# PIXIE_CHROMA_EVAL_PCB.net
KiCad netlist of a schematic drawn in EAGLE
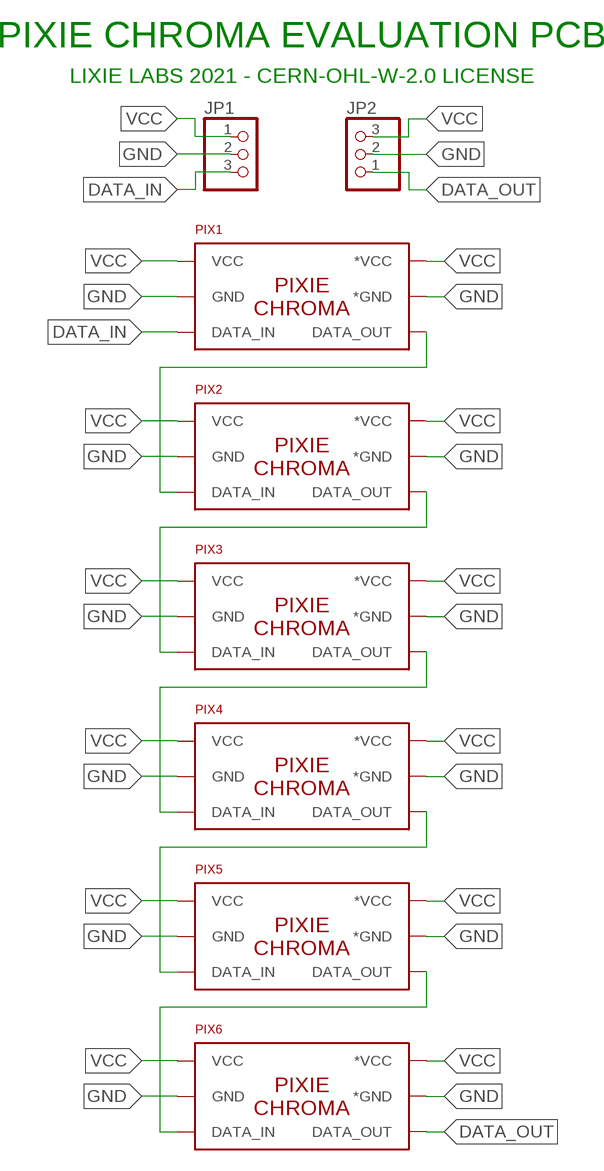
[diagram p0: schematic, sheet 1]

(export (version "E")
  (design (tool "Eeschema 10.0.6"))
  (components
    (comp (ref "JP1")
      (value "PINHD-1X3")
      (footprint "eagle-import:1X03")
      (libsource (lib "eagle-import") (part "PINHD-1X3"))
    )
    (comp (ref "JP2")
      (value "PINHD-1X3")
      (footprint "eagle-import:1X03")
      (libsource (lib "eagle-import") (part "PINHD-1X3"))
    )
    (comp (ref "PIX1")
      (value "CHROMA")
      (footprint "eagle-import:CHROMA")
      (libsource (lib "eagle-import") (part "CHROMA"))
    )
    (comp (ref "PIX2")
      (value "CHROMA")
      (footprint "eagle-import:CHROMA")
      (libsource (lib "eagle-import") (part "CHROMA"))
    )
    (comp (ref "PIX3")
      (value "CHROMA")
      (footprint "eagle-import:CHROMA")
      (libsource (lib "eagle-import") (part "CHROMA"))
    )
    (comp (ref "PIX4")
      (value "CHROMA")
      (footprint "eagle-import:CHROMA")
      (libsource (lib "eagle-import") (part "CHROMA"))
    )
    (comp (ref "PIX5")
      (value "CHROMA")
      (footprint "eagle-import:CHROMA")
      (libsource (lib "eagle-import") (part "CHROMA"))
    )
    (comp (ref "PIX6")
      (value "CHROMA")
      (footprint "eagle-import:CHROMA")
      (libsource (lib "eagle-import") (part "CHROMA"))
    )
  )
  (nets
    (net (code "1") (name "DATA_IN") (class "Default")
      (node (ref "JP1") (pin "3") (pinfunction "3_3") (pintype "passive"))
      (node (ref "PIX1") (pin "DATA_IN") (pinfunction "DATA_IN_DATA_IN") (pintype "input"))
    )
    (net (code "2") (name "DATA_OUT") (class "Default")
      (node (ref "JP2") (pin "1") (pinfunction "1_1") (pintype "passive"))
      (node (ref "PIX6") (pin "DATA_OUT") (pinfunction "DATA_OUT_DATA_OUT") (pintype "output"))
    )
    (net (code "3") (name "GND") (class "Default")
      (node (ref "JP1") (pin "2") (pinfunction "2_2") (pintype "passive"))
      (node (ref "JP2") (pin "2") (pinfunction "2_2") (pintype "passive"))
      (node (ref "PIX1") (pin "*GND") (pinfunction "*GND_*GND") (pintype "power_in"))
      (node (ref "PIX1") (pin "GND") (pinfunction "GND_GND") (pintype "power_in"))
      (node (ref "PIX2") (pin "*GND") (pinfunction "*GND_*GND") (pintype "power_in"))
      (node (ref "PIX2") (pin "GND") (pinfunction "GND_GND") (pintype "power_in"))
      (node (ref "PIX3") (pin "*GND") (pinfunction "*GND_*GND") (pintype "power_in"))
      (node (ref "PIX3") (pin "GND") (pinfunction "GND_GND") (pintype "power_in"))
      (node (ref "PIX4") (pin "*GND") (pinfunction "*GND_*GND") (pintype "power_in"))
      (node (ref "PIX4") (pin "GND") (pinfunction "GND_GND") (pintype "power_in"))
      (node (ref "PIX5") (pin "*GND") (pinfunction "*GND_*GND") (pintype "power_in"))
      (node (ref "PIX5") (pin "GND") (pinfunction "GND_GND") (pintype "power_in"))
      (node (ref "PIX6") (pin "*GND") (pinfunction "*GND_*GND") (pintype "power_in"))
      (node (ref "PIX6") (pin "GND") (pinfunction "GND_GND") (pintype "power_in"))
    )
    (net (code "4") (name "Net-(PIX1-PadDATA_OUT)") (class "Default")
      (node (ref "PIX1") (pin "DATA_OUT") (pinfunction "DATA_OUT_DATA_OUT") (pintype "output"))
      (node (ref "PIX2") (pin "DATA_IN") (pinfunction "DATA_IN_DATA_IN") (pintype "input"))
    )
    (net (code "5") (name "Net-(PIX2-PadDATA_OUT)") (class "Default")
      (node (ref "PIX2") (pin "DATA_OUT") (pinfunction "DATA_OUT_DATA_OUT") (pintype "output"))
      (node (ref "PIX3") (pin "DATA_IN") (pinfunction "DATA_IN_DATA_IN") (pintype "input"))
    )
    (net (code "6") (name "Net-(PIX3-PadDATA_OUT)") (class "Default")
      (node (ref "PIX3") (pin "DATA_OUT") (pinfunction "DATA_OUT_DATA_OUT") (pintype "output"))
      (node (ref "PIX4") (pin "DATA_IN") (pinfunction "DATA_IN_DATA_IN") (pintype "input"))
    )
    (net (code "7") (name "Net-(PIX4-PadDATA_OUT)") (class "Default")
      (node (ref "PIX4") (pin "DATA_OUT") (pinfunction "DATA_OUT_DATA_OUT") (pintype "output"))
      (node (ref "PIX5") (pin "DATA_IN") (pinfunction "DATA_IN_DATA_IN") (pintype "input"))
    )
    (net (code "8") (name "Net-(PIX5-PadDATA_OUT)") (class "Default")
      (node (ref "PIX5") (pin "DATA_OUT") (pinfunction "DATA_OUT_DATA_OUT") (pintype "output"))
      (node (ref "PIX6") (pin "DATA_IN") (pinfunction "DATA_IN_DATA_IN") (pintype "input"))
    )
    (net (code "9") (name "VCC") (class "Default")
      (node (ref "JP1") (pin "1") (pinfunction "1_1") (pintype "passive"))
      (node (ref "JP2") (pin "3") (pinfunction "3_3") (pintype "passive"))
      (node (ref "PIX1") (pin "*VCC") (pinfunction "*VCC_*VCC") (pintype "power_in"))
      (node (ref "PIX1") (pin "VCC") (pinfunction "VCC_VCC") (pintype "power_in"))
      (node (ref "PIX2") (pin "*VCC") (pinfunction "*VCC_*VCC") (pintype "power_in"))
      (node (ref "PIX2") (pin "VCC") (pinfunction "VCC_VCC") (pintype "power_in"))
      (node (ref "PIX3") (pin "*VCC") (pinfunction "*VCC_*VCC") (pintype "power_in"))
      (node (ref "PIX3") (pin "VCC") (pinfunction "VCC_VCC") (pintype "power_in"))
      (node (ref "PIX4") (pin "*VCC") (pinfunction "*VCC_*VCC") (pintype "power_in"))
      (node (ref "PIX4") (pin "VCC") (pinfunction "VCC_VCC") (pintype "power_in"))
      (node (ref "PIX5") (pin "*VCC") (pinfunction "*VCC_*VCC") (pintype "power_in"))
      (node (ref "PIX5") (pin "VCC") (pinfunction "VCC_VCC") (pintype "power_in"))
      (node (ref "PIX6") (pin "*VCC") (pinfunction "*VCC_*VCC") (pintype "power_in"))
      (node (ref "PIX6") (pin "VCC") (pinfunction "VCC_VCC") (pintype "power_in"))
    )
  )
)
